# main.net
KiCad netlist of a schematic drawn in EAGLE
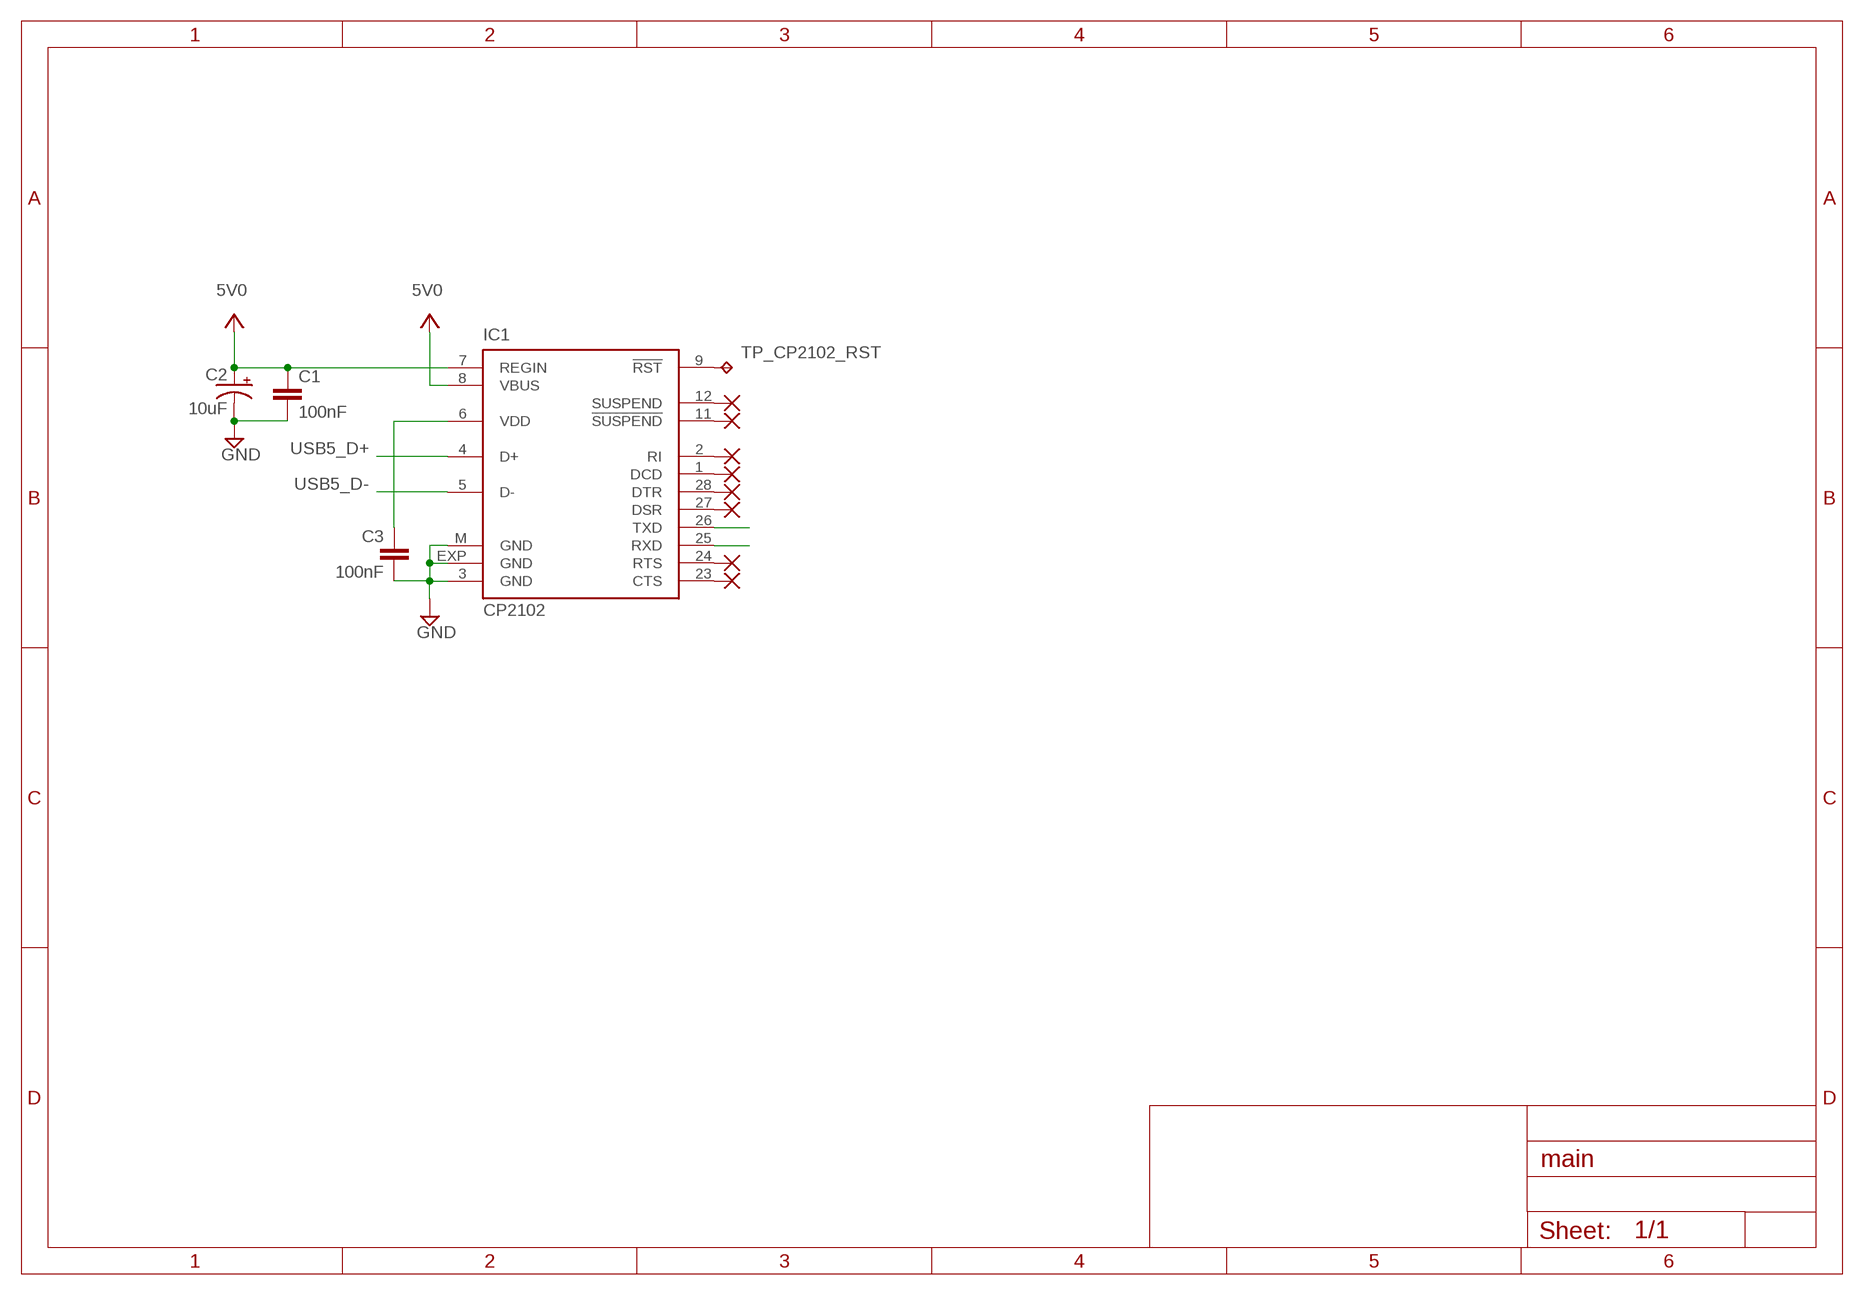
[diagram p0: schematic, sheet 1]

(export (version "E")
  (design (tool "Eeschema 10.0.6"))
  (components
    (comp (ref "C1")
      (value "100nF")
      (footprint "eagle-import:RCL_C1206")
      (libsource (lib "eagle-import") (part "RCL_C-EUC1206"))
    )
    (comp (ref "C2")
      (value "10uF")
      (footprint "eagle-import:RCL_085CS_1AW")
      (libsource (lib "eagle-import") (part "RCL_CPOL-US085CS-1AW"))
    )
    (comp (ref "C3")
      (value "100nF")
      (footprint "eagle-import:RCL_C1206")
      (libsource (lib "eagle-import") (part "RCL_C-EUC1206"))
    )
    (comp (ref "IC1")
      (value "CP2102")
      (footprint "eagle-import:MLP28")
      (fields (field (name "MF") "FARNELL") (field (name "MPN") "CP2102-GM"))
      (libsource (lib "eagle-import") (part "CP2102"))
    )
    (comp (ref "PAD1")
      (value "WIREPADSMD1,27-254")
      (footprint "eagle-import:SMD1,27-2,54")
      (libsource (lib "eagle-import") (part "WIREPADSMD1,27-254"))
    )
    (comp (ref "PAD2")
      (value "WIREPADSMD1,27-254")
      (footprint "eagle-import:SMD1,27-2,54")
      (libsource (lib "eagle-import") (part "WIREPADSMD1,27-254"))
    )
    (comp (ref "PAD3")
      (value "WIREPADSMD1,27-254")
      (footprint "eagle-import:SMD1,27-2,54")
      (libsource (lib "eagle-import") (part "WIREPADSMD1,27-254"))
    )
    (comp (ref "PAD4")
      (value "WIREPADSMD1,27-254")
      (footprint "eagle-import:SMD1,27-2,54")
      (libsource (lib "eagle-import") (part "WIREPADSMD1,27-254"))
    )
    (comp (ref "PAD5")
      (value "WIREPADSMD1,27-254")
      (footprint "eagle-import:SMD1,27-2,54")
      (libsource (lib "eagle-import") (part "WIREPADSMD1,27-254"))
    )
    (comp (ref "PAD6")
      (value "WIREPADSMD1,27-254")
      (footprint "eagle-import:SMD1,27-2,54")
      (libsource (lib "eagle-import") (part "WIREPADSMD1,27-254"))
    )
    (comp (ref "PAD7")
      (value "WIREPADSMD1,27-254")
      (footprint "eagle-import:SMD1,27-2,54")
      (libsource (lib "eagle-import") (part "WIREPADSMD1,27-254"))
    )
    (comp (ref "PAD8")
      (value "WIREPADSMD1,27-254")
      (footprint "eagle-import:SMD1,27-2,54")
      (libsource (lib "eagle-import") (part "WIREPADSMD1,27-254"))
    )
    (comp (ref "TP_CP2102_RST")
      (value "TPB1,27")
      (footprint "eagle-import:B1,27")
      (libsource (lib "eagle-import") (part "TPB1,27"))
    )
  )
  (nets
    (net (code "1") (name "/USB5_D+") (class "Default")
      (node (ref "IC1") (pin "4") (pinfunction "D+_4") (pintype "bidirectional"))
    )
    (net (code "2") (name "/USB5_D-") (class "Default")
      (node (ref "IC1") (pin "5") (pinfunction "D-_5") (pintype "bidirectional"))
    )
    (net (code "3") (name "5V0") (class "Default")
      (node (ref "C1") (pin "1") (pinfunction "1_1") (pintype "passive"))
      (node (ref "C2") (pin "+") (pinfunction "+_+") (pintype "passive"))
      (node (ref "IC1") (pin "7") (pinfunction "REGIN_7") (pintype "passive"))
      (node (ref "IC1") (pin "8") (pinfunction "VBUS_8") (pintype "input"))
    )
    (net (code "4") (name "GND") (class "Default")
      (node (ref "C1") (pin "2") (pinfunction "2_2") (pintype "passive"))
      (node (ref "C2") (pin "-") (pinfunction "-_-") (pintype "passive"))
      (node (ref "C3") (pin "2") (pinfunction "2_2") (pintype "passive"))
      (node (ref "IC1") (pin "3") (pinfunction "GND_3") (pintype "power_in"))
      (node (ref "IC1") (pin "EXP") (pinfunction "GND_EXP") (pintype "power_in"))
      (node (ref "IC1") (pin "M") (pinfunction "GND_M") (pintype "power_in"))
    )
    (net (code "5") (name "Net-(IC1-CTS)") (class "Default")
      (node (ref "IC1") (pin "23") (pinfunction "CTS_23") (pintype "input"))
      (node (ref "PAD6") (pin "1") (pinfunction "P_1") (pintype "passive"))
    )
    (net (code "6") (name "Net-(IC1-DCD)") (class "Default")
      (node (ref "IC1") (pin "1") (pinfunction "DCD_1") (pintype "input"))
      (node (ref "PAD2") (pin "1") (pinfunction "P_1") (pintype "passive"))
    )
    (net (code "7") (name "Net-(IC1-DSR)") (class "Default")
      (node (ref "IC1") (pin "27") (pinfunction "DSR_27") (pintype "input"))
      (node (ref "PAD4") (pin "1") (pinfunction "P_1") (pintype "passive"))
    )
    (net (code "8") (name "Net-(IC1-DTR)") (class "Default")
      (node (ref "IC1") (pin "28") (pinfunction "DTR_28") (pintype "output"))
      (node (ref "PAD3") (pin "1") (pinfunction "P_1") (pintype "passive"))
    )
    (net (code "9") (name "Net-(IC1-RI)") (class "Default")
      (node (ref "IC1") (pin "2") (pinfunction "RI_2") (pintype "input"))
      (node (ref "PAD1") (pin "1") (pinfunction "P_1") (pintype "passive"))
    )
    (net (code "10") (name "Net-(IC1-RTS)") (class "Default")
      (node (ref "IC1") (pin "24") (pinfunction "RTS_24") (pintype "output"))
      (node (ref "PAD5") (pin "1") (pinfunction "P_1") (pintype "passive"))
    )
    (net (code "11") (name "Net-(IC1-SUSPEND)") (class "Default")
      (node (ref "IC1") (pin "12") (pinfunction "SUSPEND_12") (pintype "output"))
      (node (ref "PAD7") (pin "1") (pinfunction "P_1") (pintype "passive"))
    )
    (net (code "12") (name "Net-(IC1-VDD)") (class "Default")
      (node (ref "C3") (pin "1") (pinfunction "1_1") (pintype "passive"))
      (node (ref "IC1") (pin "6") (pinfunction "VDD_6") (pintype "power_in"))
    )
    (net (code "13") (name "Net-(IC1-~{RST})") (class "Default")
      (node (ref "IC1") (pin "9") (pinfunction "~{RST}_9") (pintype "bidirectional"))
      (node (ref "TP_CP2102_RST") (pin "TP") (pinfunction "TP_TP") (pintype "input"))
    )
    (net (code "14") (name "Net-(IC1-~{SUSPEND})") (class "Default")
      (node (ref "IC1") (pin "11") (pinfunction "~{SUSPEND}_11") (pintype "output"))
      (node (ref "PAD8") (pin "1") (pinfunction "P_1") (pintype "passive"))
    )
    (net (code "15") (name "unconnected-(IC1-RXD-Pad25)") (class "Default")
      (node (ref "IC1") (pin "25") (pinfunction "RXD_25") (pintype "input"))
    )
    (net (code "16") (name "unconnected-(IC1-TXD-Pad26)") (class "Default")
      (node (ref "IC1") (pin "26") (pinfunction "TXD_26") (pintype "output"))
    )
  )
)
